# BSK4.net
KiCad netlist of a schematic drawn in EAGLE
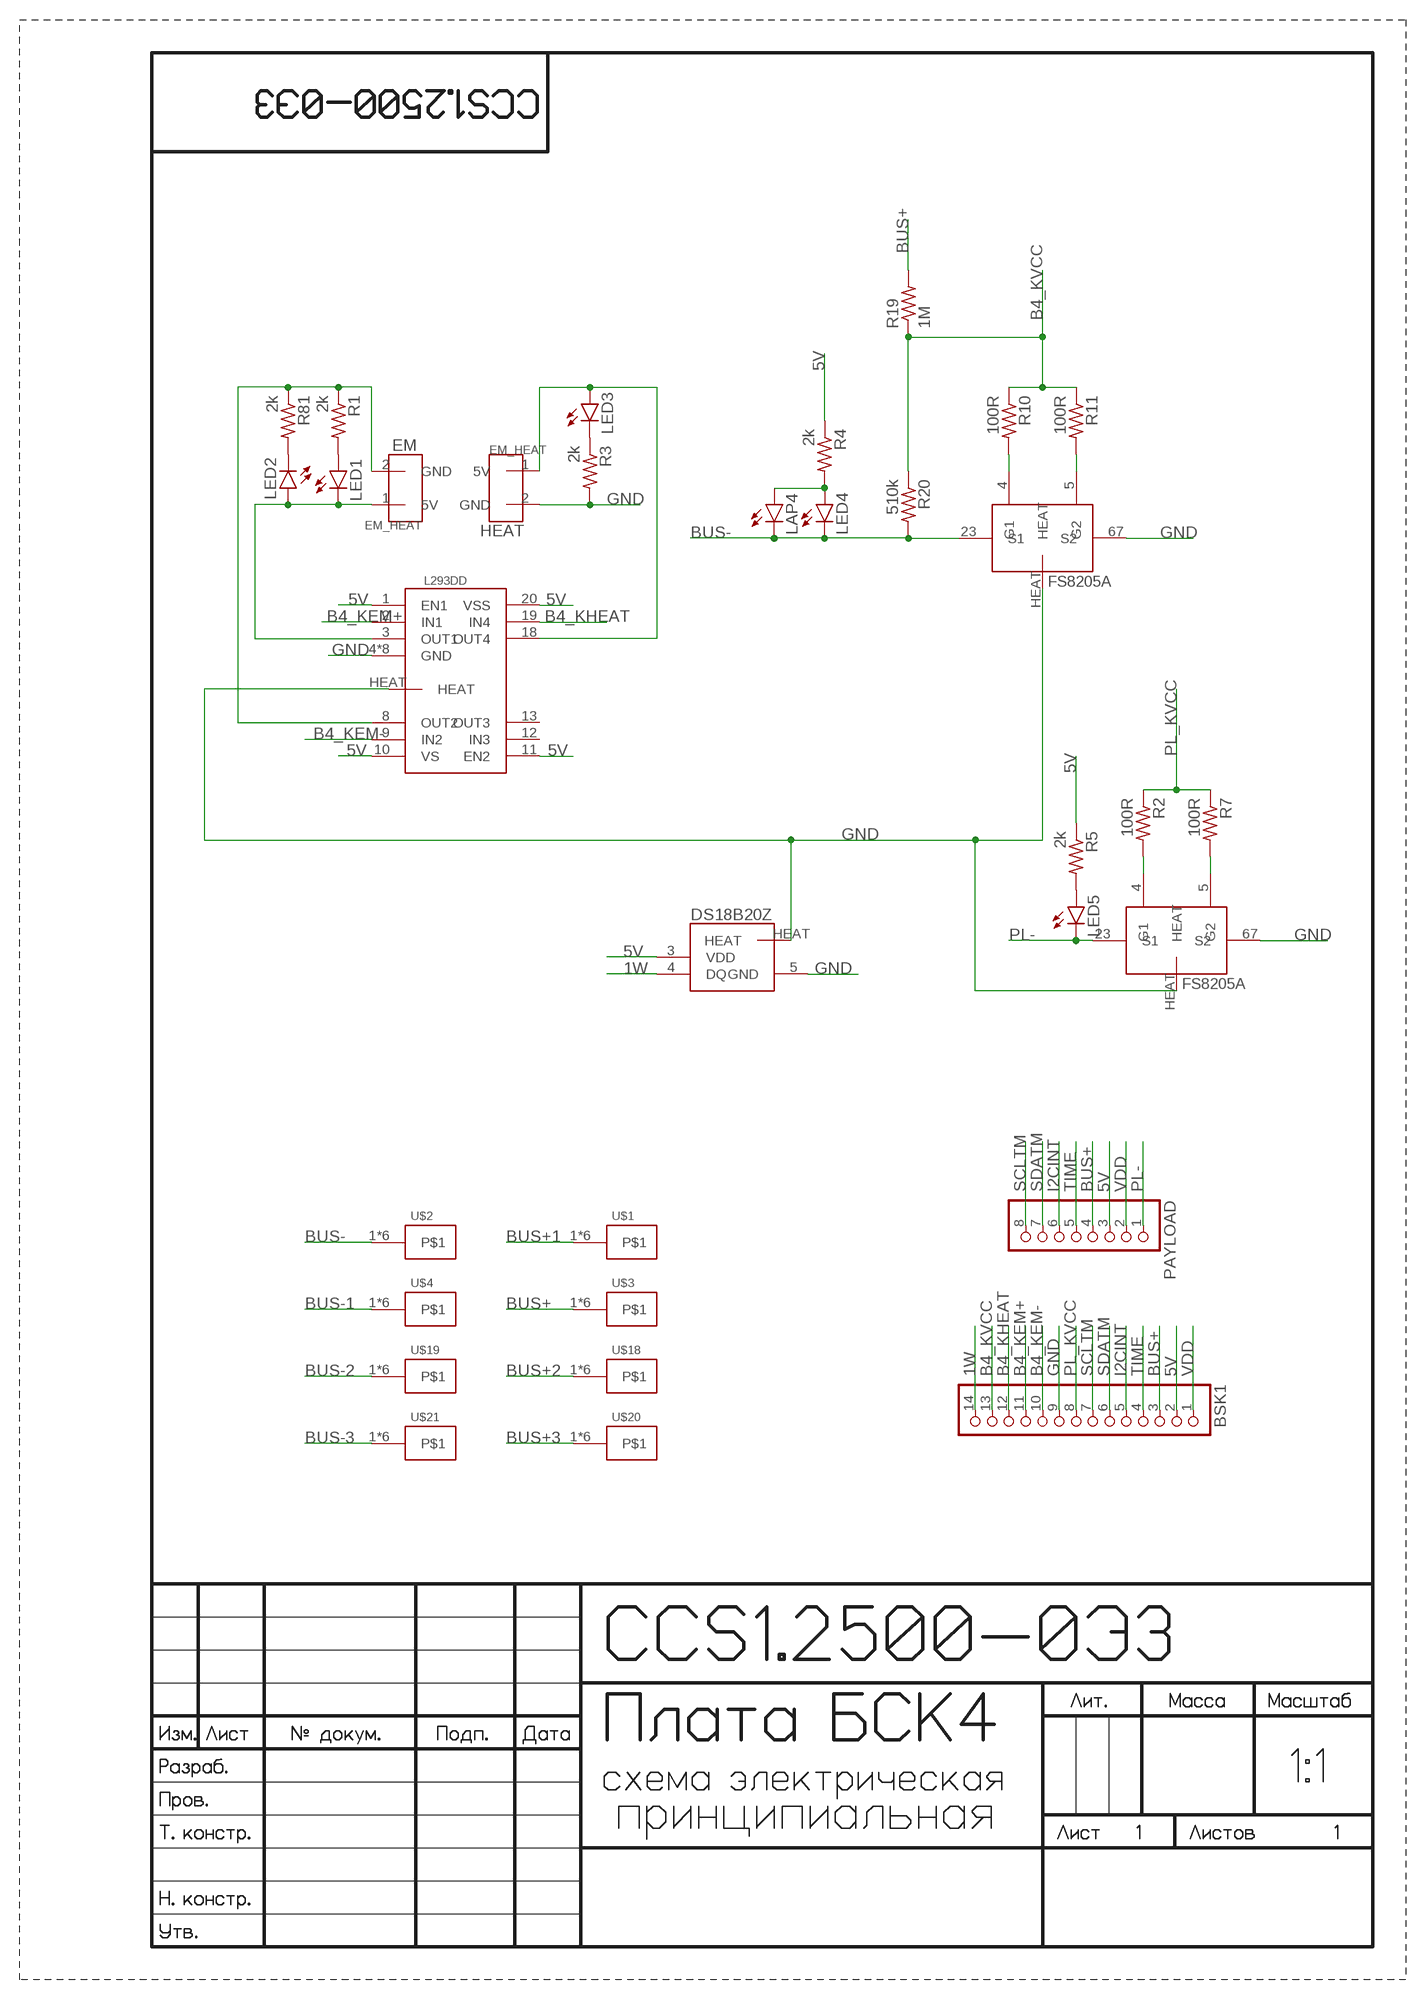
[diagram p0: schematic, sheet 1]

(export (version "E")
  (design (tool "Eeschema 10.0.6"))
  (components
    (comp (ref "BSK1")
      (value "PINHD-1X14")
      (footprint "eagle-import:1X14")
      (libsource (lib "eagle-import") (part "PINHD-1X14"))
    )
    (comp (ref "DS18B20Z")
      (value "DS18B20Z")
      (footprint "eagle-import:DS18B20Z")
      (libsource (lib "eagle-import") (part "DS18B20Z"))
    )
    (comp (ref "FS8205A#1")
      (value "FS8205A+")
      (footprint "eagle-import:FS8205A+")
      (libsource (lib "eagle-import") (part "FS8205A+"))
    )
    (comp (ref "FS8205A#2")
      (value "FS8205A+")
      (footprint "eagle-import:FS8205A+")
      (libsource (lib "eagle-import") (part "FS8205A+"))
    )
    (comp (ref "L293DD")
      (value "L293DD")
      (footprint "eagle-import:L293DD")
      (libsource (lib "eagle-import") (part "L293DD"))
    )
    (comp (ref "LAP4")
      (value "LAP4-BOTTOM")
      (footprint "eagle-import:P47F-BOTTOM")
      (libsource (lib "eagle-import") (part "P4-BOTTOMLA"))
    )
    (comp (ref "LED1")
      (value "LEDCHIPLED_0603")
      (footprint "eagle-import:CHIPLED_0603")
      (libsource (lib "eagle-import") (part "LEDCHIPLED_0603"))
    )
    (comp (ref "LED2")
      (value "LEDCHIPLED_0603")
      (footprint "eagle-import:CHIPLED_0603")
      (libsource (lib "eagle-import") (part "LEDCHIPLED_0603"))
    )
    (comp (ref "LED3")
      (value "LEDCHIPLED_0603")
      (footprint "eagle-import:CHIPLED_0603")
      (libsource (lib "eagle-import") (part "LEDCHIPLED_0603"))
    )
    (comp (ref "LED4")
      (value "LEDCHIPLED_0603")
      (footprint "eagle-import:CHIPLED_0603")
      (libsource (lib "eagle-import") (part "LEDCHIPLED_0603"))
    )
    (comp (ref "LED5")
      (value "LEDCHIPLED_0603")
      (footprint "eagle-import:CHIPLED_0603")
      (libsource (lib "eagle-import") (part "LEDCHIPLED_0603"))
    )
    (comp (ref "PAYLOAD")
      (value "PINHD-1X8")
      (footprint "eagle-import:1X08")
      (libsource (lib "eagle-import") (part "PINHD-1X8"))
    )
    (comp (ref "R1")
      (value "2k")
      (footprint "eagle-import:R0603")
      (libsource (lib "eagle-import") (part "R-US_R0603"))
    )
    (comp (ref "R2")
      (value "100R")
      (footprint "eagle-import:R0603")
      (libsource (lib "eagle-import") (part "R-US_R0603"))
    )
    (comp (ref "R3")
      (value "2k")
      (footprint "eagle-import:R0603")
      (libsource (lib "eagle-import") (part "R-US_R0603"))
    )
    (comp (ref "R4")
      (value "2k")
      (footprint "eagle-import:R0603")
      (libsource (lib "eagle-import") (part "R-US_R0603"))
    )
    (comp (ref "R5")
      (value "2k")
      (footprint "eagle-import:R0603")
      (libsource (lib "eagle-import") (part "R-US_R0603"))
    )
    (comp (ref "R7")
      (value "100R")
      (footprint "eagle-import:R0603")
      (libsource (lib "eagle-import") (part "R-US_R0603"))
    )
    (comp (ref "R10")
      (value "100R")
      (footprint "eagle-import:R0603")
      (libsource (lib "eagle-import") (part "R-US_R0603"))
    )
    (comp (ref "R11")
      (value "100R")
      (footprint "eagle-import:R0603")
      (libsource (lib "eagle-import") (part "R-US_R0603"))
    )
    (comp (ref "R19")
      (value "1M")
      (footprint "eagle-import:R0603")
      (libsource (lib "eagle-import") (part "R-US_R0603"))
    )
    (comp (ref "R20")
      (value "510k")
      (footprint "eagle-import:R0603")
      (libsource (lib "eagle-import") (part "R-US_R0603"))
    )
    (comp (ref "R81")
      (value "2k")
      (footprint "eagle-import:R0603")
      (libsource (lib "eagle-import") (part "R-US_R0603"))
    )
    (comp (ref "U$1")
      (value "KCONNECT")
      (footprint "eagle-import:KCONNECT")
      (libsource (lib "eagle-import") (part "KCONNECT"))
    )
    (comp (ref "U$2")
      (value "KCONNECT")
      (footprint "eagle-import:KCONNECT")
      (libsource (lib "eagle-import") (part "KCONNECT"))
    )
    (comp (ref "U$3")
      (value "KCONNECT")
      (footprint "eagle-import:KCONNECT")
      (libsource (lib "eagle-import") (part "KCONNECT"))
    )
    (comp (ref "U$4")
      (value "KCONNECT")
      (footprint "eagle-import:KCONNECT")
      (libsource (lib "eagle-import") (part "KCONNECT"))
    )
    (comp (ref "U$6")
      (value "EM_HEAT")
      (footprint "eagle-import:EM_HEAT")
      (libsource (lib "eagle-import") (part "EM_HEAT"))
    )
    (comp (ref "U$7")
      (value "EM_HEAT")
      (footprint "eagle-import:EM_HEAT")
      (libsource (lib "eagle-import") (part "EM_HEAT"))
    )
    (comp (ref "U$18")
      (value "KCONNECT")
      (footprint "eagle-import:KCONNECT")
      (libsource (lib "eagle-import") (part "KCONNECT"))
    )
    (comp (ref "U$19")
      (value "KCONNECT")
      (footprint "eagle-import:KCONNECT")
      (libsource (lib "eagle-import") (part "KCONNECT"))
    )
    (comp (ref "U$20")
      (value "KCONNECT")
      (footprint "eagle-import:KCONNECT")
      (libsource (lib "eagle-import") (part "KCONNECT"))
    )
    (comp (ref "U$21")
      (value "KCONNECT")
      (footprint "eagle-import:KCONNECT")
      (libsource (lib "eagle-import") (part "KCONNECT"))
    )
  )
  (nets
    (net (code "1") (name "/1W") (class "Default")
      (node (ref "BSK1") (pin "14") (pinfunction "14_14") (pintype "passive"))
      (node (ref "DS18B20Z") (pin "4") (pinfunction "DQ_4") (pintype "bidirectional"))
    )
    (net (code "2") (name "/5V") (class "Default")
      (node (ref "BSK1") (pin "2") (pinfunction "2_2") (pintype "passive"))
      (node (ref "DS18B20Z") (pin "3") (pinfunction "VDD_3") (pintype "bidirectional"))
      (node (ref "L293DD") (pin "1") (pinfunction "EN1_1") (pintype "bidirectional"))
      (node (ref "L293DD") (pin "10") (pinfunction "VS_10") (pintype "bidirectional"))
      (node (ref "L293DD") (pin "11") (pinfunction "EN2_11") (pintype "bidirectional"))
      (node (ref "L293DD") (pin "20") (pinfunction "VSS_20") (pintype "bidirectional"))
      (node (ref "PAYLOAD") (pin "3") (pinfunction "3_3") (pintype "passive"))
      (node (ref "R4") (pin "1") (pinfunction "1_1") (pintype "passive"))
      (node (ref "R5") (pin "1") (pinfunction "1_1") (pintype "passive"))
    )
    (net (code "3") (name "/B4_KEM+") (class "Default")
      (node (ref "BSK1") (pin "11") (pinfunction "11_11") (pintype "passive"))
      (node (ref "L293DD") (pin "2") (pinfunction "IN1_2") (pintype "bidirectional"))
    )
    (net (code "4") (name "/B4_KEM-") (class "Default")
      (node (ref "BSK1") (pin "10") (pinfunction "10_10") (pintype "passive"))
      (node (ref "L293DD") (pin "9") (pinfunction "IN2_9") (pintype "bidirectional"))
    )
    (net (code "5") (name "/B4_KHEAT") (class "Default")
      (node (ref "BSK1") (pin "12") (pinfunction "12_12") (pintype "passive"))
      (node (ref "L293DD") (pin "19") (pinfunction "IN4_19") (pintype "bidirectional"))
    )
    (net (code "6") (name "/B4_KVCC") (class "Default")
      (node (ref "BSK1") (pin "13") (pinfunction "13_13") (pintype "passive"))
      (node (ref "R10") (pin "1") (pinfunction "1_1") (pintype "passive"))
      (node (ref "R11") (pin "1") (pinfunction "1_1") (pintype "passive"))
      (node (ref "R19") (pin "1") (pinfunction "1_1") (pintype "passive"))
      (node (ref "R20") (pin "1") (pinfunction "1_1") (pintype "passive"))
    )
    (net (code "7") (name "/BUS+") (class "Default")
      (node (ref "BSK1") (pin "3") (pinfunction "3_3") (pintype "passive"))
      (node (ref "PAYLOAD") (pin "4") (pinfunction "4_4") (pintype "passive"))
      (node (ref "R19") (pin "2") (pinfunction "2_2") (pintype "passive"))
      (node (ref "U$3") (pin "1") (pinfunction "P$1_1") (pintype "bidirectional"))
      (node (ref "U$3") (pin "2") (pinfunction "P$1_2") (pintype "bidirectional"))
      (node (ref "U$3") (pin "3") (pinfunction "P$1_3") (pintype "bidirectional"))
      (node (ref "U$3") (pin "4") (pinfunction "P$1_4") (pintype "bidirectional"))
      (node (ref "U$3") (pin "P$1") (pinfunction "P$1_P$1") (pintype "bidirectional"))
      (node (ref "U$3") (pin "P$2") (pinfunction "P$1_P$2") (pintype "bidirectional"))
    )
    (net (code "8") (name "/BUS+1") (class "Default")
      (node (ref "U$1") (pin "1") (pinfunction "P$1_1") (pintype "bidirectional"))
      (node (ref "U$1") (pin "2") (pinfunction "P$1_2") (pintype "bidirectional"))
      (node (ref "U$1") (pin "3") (pinfunction "P$1_3") (pintype "bidirectional"))
      (node (ref "U$1") (pin "4") (pinfunction "P$1_4") (pintype "bidirectional"))
      (node (ref "U$1") (pin "P$1") (pinfunction "P$1_P$1") (pintype "bidirectional"))
      (node (ref "U$1") (pin "P$2") (pinfunction "P$1_P$2") (pintype "bidirectional"))
    )
    (net (code "9") (name "/BUS+2") (class "Default")
      (node (ref "U$18") (pin "1") (pinfunction "P$1_1") (pintype "bidirectional"))
      (node (ref "U$18") (pin "2") (pinfunction "P$1_2") (pintype "bidirectional"))
      (node (ref "U$18") (pin "3") (pinfunction "P$1_3") (pintype "bidirectional"))
      (node (ref "U$18") (pin "4") (pinfunction "P$1_4") (pintype "bidirectional"))
      (node (ref "U$18") (pin "P$1") (pinfunction "P$1_P$1") (pintype "bidirectional"))
      (node (ref "U$18") (pin "P$2") (pinfunction "P$1_P$2") (pintype "bidirectional"))
    )
    (net (code "10") (name "/BUS+3") (class "Default")
      (node (ref "U$20") (pin "1") (pinfunction "P$1_1") (pintype "bidirectional"))
      (node (ref "U$20") (pin "2") (pinfunction "P$1_2") (pintype "bidirectional"))
      (node (ref "U$20") (pin "3") (pinfunction "P$1_3") (pintype "bidirectional"))
      (node (ref "U$20") (pin "4") (pinfunction "P$1_4") (pintype "bidirectional"))
      (node (ref "U$20") (pin "P$1") (pinfunction "P$1_P$1") (pintype "bidirectional"))
      (node (ref "U$20") (pin "P$2") (pinfunction "P$1_P$2") (pintype "bidirectional"))
    )
    (net (code "11") (name "/BUS-") (class "Default")
      (node (ref "FS8205A#1") (pin "23") (pinfunction "S1_23") (pintype "bidirectional"))
      (node (ref "LAP4") (pin "C") (pinfunction "C_C") (pintype "passive"))
      (node (ref "LED4") (pin "C") (pinfunction "C_C") (pintype "passive"))
      (node (ref "R20") (pin "2") (pinfunction "2_2") (pintype "passive"))
      (node (ref "U$2") (pin "1") (pinfunction "P$1_1") (pintype "bidirectional"))
      (node (ref "U$2") (pin "2") (pinfunction "P$1_2") (pintype "bidirectional"))
      (node (ref "U$2") (pin "3") (pinfunction "P$1_3") (pintype "bidirectional"))
      (node (ref "U$2") (pin "4") (pinfunction "P$1_4") (pintype "bidirectional"))
      (node (ref "U$2") (pin "P$1") (pinfunction "P$1_P$1") (pintype "bidirectional"))
      (node (ref "U$2") (pin "P$2") (pinfunction "P$1_P$2") (pintype "bidirectional"))
    )
    (net (code "12") (name "/BUS-1") (class "Default")
      (node (ref "U$4") (pin "1") (pinfunction "P$1_1") (pintype "bidirectional"))
      (node (ref "U$4") (pin "2") (pinfunction "P$1_2") (pintype "bidirectional"))
      (node (ref "U$4") (pin "3") (pinfunction "P$1_3") (pintype "bidirectional"))
      (node (ref "U$4") (pin "4") (pinfunction "P$1_4") (pintype "bidirectional"))
      (node (ref "U$4") (pin "P$1") (pinfunction "P$1_P$1") (pintype "bidirectional"))
      (node (ref "U$4") (pin "P$2") (pinfunction "P$1_P$2") (pintype "bidirectional"))
    )
    (net (code "13") (name "/BUS-2") (class "Default")
      (node (ref "U$19") (pin "1") (pinfunction "P$1_1") (pintype "bidirectional"))
      (node (ref "U$19") (pin "2") (pinfunction "P$1_2") (pintype "bidirectional"))
      (node (ref "U$19") (pin "3") (pinfunction "P$1_3") (pintype "bidirectional"))
      (node (ref "U$19") (pin "4") (pinfunction "P$1_4") (pintype "bidirectional"))
      (node (ref "U$19") (pin "P$1") (pinfunction "P$1_P$1") (pintype "bidirectional"))
      (node (ref "U$19") (pin "P$2") (pinfunction "P$1_P$2") (pintype "bidirectional"))
    )
    (net (code "14") (name "/BUS-3") (class "Default")
      (node (ref "U$21") (pin "1") (pinfunction "P$1_1") (pintype "bidirectional"))
      (node (ref "U$21") (pin "2") (pinfunction "P$1_2") (pintype "bidirectional"))
      (node (ref "U$21") (pin "3") (pinfunction "P$1_3") (pintype "bidirectional"))
      (node (ref "U$21") (pin "4") (pinfunction "P$1_4") (pintype "bidirectional"))
      (node (ref "U$21") (pin "P$1") (pinfunction "P$1_P$1") (pintype "bidirectional"))
      (node (ref "U$21") (pin "P$2") (pinfunction "P$1_P$2") (pintype "bidirectional"))
    )
    (net (code "15") (name "/GND") (class "Default")
      (node (ref "BSK1") (pin "9") (pinfunction "9_9") (pintype "passive"))
      (node (ref "DS18B20Z") (pin "5") (pinfunction "GND_5") (pintype "bidirectional"))
      (node (ref "DS18B20Z") (pin "HEAT") (pinfunction "HEAT_HEAT") (pintype "bidirectional"))
      (node (ref "FS8205A#1") (pin "67") (pinfunction "S2_67") (pintype "bidirectional"))
      (node (ref "FS8205A#1") (pin "HEAT") (pinfunction "HEAT_HEAT") (pintype "bidirectional"))
      (node (ref "FS8205A#2") (pin "67") (pinfunction "S2_67") (pintype "bidirectional"))
      (node (ref "FS8205A#2") (pin "HEAT") (pinfunction "HEAT_HEAT") (pintype "bidirectional"))
      (node (ref "L293DD") (pin "14") (pinfunction "GND_14") (pintype "bidirectional"))
      (node (ref "L293DD") (pin "15") (pinfunction "GND_15") (pintype "bidirectional"))
      (node (ref "L293DD") (pin "16") (pinfunction "GND_16") (pintype "bidirectional"))
      (node (ref "L293DD") (pin "17") (pinfunction "GND_17") (pintype "bidirectional"))
      (node (ref "L293DD") (pin "4") (pinfunction "GND_4") (pintype "bidirectional"))
      (node (ref "L293DD") (pin "5") (pinfunction "GND_5") (pintype "bidirectional"))
      (node (ref "L293DD") (pin "6") (pinfunction "GND_6") (pintype "bidirectional"))
      (node (ref "L293DD") (pin "7") (pinfunction "GND_7") (pintype "bidirectional"))
      (node (ref "L293DD") (pin "HEAT") (pinfunction "HEAT_HEAT") (pintype "bidirectional"))
      (node (ref "R3") (pin "2") (pinfunction "2_2") (pintype "passive"))
      (node (ref "U$7") (pin "2") (pinfunction "GND_2") (pintype "bidirectional"))
    )
    (net (code "16") (name "/I2CINT") (class "Default")
      (node (ref "BSK1") (pin "5") (pinfunction "5_5") (pintype "passive"))
      (node (ref "PAYLOAD") (pin "6") (pinfunction "6_6") (pintype "passive"))
    )
    (net (code "17") (name "/PL-") (class "Default")
      (node (ref "FS8205A#2") (pin "23") (pinfunction "S1_23") (pintype "bidirectional"))
      (node (ref "LED5") (pin "C") (pinfunction "C_C") (pintype "passive"))
      (node (ref "PAYLOAD") (pin "1") (pinfunction "1_1") (pintype "passive"))
    )
    (net (code "18") (name "/PL_KVCC") (class "Default")
      (node (ref "BSK1") (pin "8") (pinfunction "8_8") (pintype "passive"))
      (node (ref "R2") (pin "1") (pinfunction "1_1") (pintype "passive"))
      (node (ref "R7") (pin "1") (pinfunction "1_1") (pintype "passive"))
    )
    (net (code "19") (name "/SCLTM") (class "Default")
      (node (ref "BSK1") (pin "7") (pinfunction "7_7") (pintype "passive"))
      (node (ref "PAYLOAD") (pin "8") (pinfunction "8_8") (pintype "passive"))
    )
    (net (code "20") (name "/SDATM") (class "Default")
      (node (ref "BSK1") (pin "6") (pinfunction "6_6") (pintype "passive"))
      (node (ref "PAYLOAD") (pin "7") (pinfunction "7_7") (pintype "passive"))
    )
    (net (code "21") (name "/TIME") (class "Default")
      (node (ref "BSK1") (pin "4") (pinfunction "4_4") (pintype "passive"))
      (node (ref "PAYLOAD") (pin "5") (pinfunction "5_5") (pintype "passive"))
    )
    (net (code "22") (name "/VDD") (class "Default")
      (node (ref "BSK1") (pin "1") (pinfunction "1_1") (pintype "passive"))
      (node (ref "PAYLOAD") (pin "2") (pinfunction "2_2") (pintype "passive"))
    )
    (net (code "23") (name "Net-(FS8205A#1-G1)") (class "Default")
      (node (ref "FS8205A#1") (pin "4") (pinfunction "G1_4") (pintype "bidirectional"))
      (node (ref "R10") (pin "2") (pinfunction "2_2") (pintype "passive"))
    )
    (net (code "24") (name "Net-(FS8205A#1-G2)") (class "Default")
      (node (ref "FS8205A#1") (pin "5") (pinfunction "G2_5") (pintype "bidirectional"))
      (node (ref "R11") (pin "2") (pinfunction "2_2") (pintype "passive"))
    )
    (net (code "25") (name "Net-(FS8205A#2-G1)") (class "Default")
      (node (ref "FS8205A#2") (pin "4") (pinfunction "G1_4") (pintype "bidirectional"))
      (node (ref "R2") (pin "2") (pinfunction "2_2") (pintype "passive"))
    )
    (net (code "26") (name "Net-(FS8205A#2-G2)") (class "Default")
      (node (ref "FS8205A#2") (pin "5") (pinfunction "G2_5") (pintype "bidirectional"))
      (node (ref "R7") (pin "2") (pinfunction "2_2") (pintype "passive"))
    )
    (net (code "27") (name "Net-(L293DD-OUT1)") (class "Default")
      (node (ref "L293DD") (pin "3") (pinfunction "OUT1_3") (pintype "bidirectional"))
      (node (ref "LED1") (pin "C") (pinfunction "C_C") (pintype "passive"))
      (node (ref "LED2") (pin "A") (pinfunction "A_A") (pintype "passive"))
      (node (ref "U$6") (pin "1") (pinfunction "5V_1") (pintype "bidirectional"))
    )
    (net (code "28") (name "Net-(L293DD-OUT2)") (class "Default")
      (node (ref "L293DD") (pin "8") (pinfunction "OUT2_8") (pintype "bidirectional"))
      (node (ref "R1") (pin "1") (pinfunction "1_1") (pintype "passive"))
      (node (ref "R81") (pin "1") (pinfunction "1_1") (pintype "passive"))
      (node (ref "U$6") (pin "2") (pinfunction "GND_2") (pintype "bidirectional"))
    )
    (net (code "29") (name "Net-(L293DD-OUT4)") (class "Default")
      (node (ref "L293DD") (pin "18") (pinfunction "OUT4_18") (pintype "bidirectional"))
      (node (ref "LED3") (pin "A") (pinfunction "A_A") (pintype "passive"))
      (node (ref "U$7") (pin "1") (pinfunction "5V_1") (pintype "bidirectional"))
    )
    (net (code "30") (name "Net-(LAP4-PadA)") (class "Default")
      (node (ref "LAP4") (pin "A") (pinfunction "A_A") (pintype "passive"))
      (node (ref "LED4") (pin "A") (pinfunction "A_A") (pintype "passive"))
      (node (ref "R4") (pin "2") (pinfunction "2_2") (pintype "passive"))
    )
    (net (code "31") (name "Net-(LED1-PadA)") (class "Default")
      (node (ref "LED1") (pin "A") (pinfunction "A_A") (pintype "passive"))
      (node (ref "R1") (pin "2") (pinfunction "2_2") (pintype "passive"))
    )
    (net (code "32") (name "Net-(LED2-PadC)") (class "Default")
      (node (ref "LED2") (pin "C") (pinfunction "C_C") (pintype "passive"))
      (node (ref "R81") (pin "2") (pinfunction "2_2") (pintype "passive"))
    )
    (net (code "33") (name "Net-(LED3-PadC)") (class "Default")
      (node (ref "LED3") (pin "C") (pinfunction "C_C") (pintype "passive"))
      (node (ref "R3") (pin "1") (pinfunction "1_1") (pintype "passive"))
    )
    (net (code "34") (name "Net-(LED5-PadA)") (class "Default")
      (node (ref "LED5") (pin "A") (pinfunction "A_A") (pintype "passive"))
      (node (ref "R5") (pin "2") (pinfunction "2_2") (pintype "passive"))
    )
    (net (code "35") (name "unconnected-(L293DD-IN3-Pad12)") (class "Default")
      (node (ref "L293DD") (pin "12") (pinfunction "IN3_12") (pintype "bidirectional"))
    )
    (net (code "36") (name "unconnected-(L293DD-OUT3-Pad13)") (class "Default")
      (node (ref "L293DD") (pin "13") (pinfunction "OUT3_13") (pintype "bidirectional"))
    )
  )
)
